# ESP-01_Tamer_-_V1_1.net
KiCad netlist of a schematic drawn in EAGLE
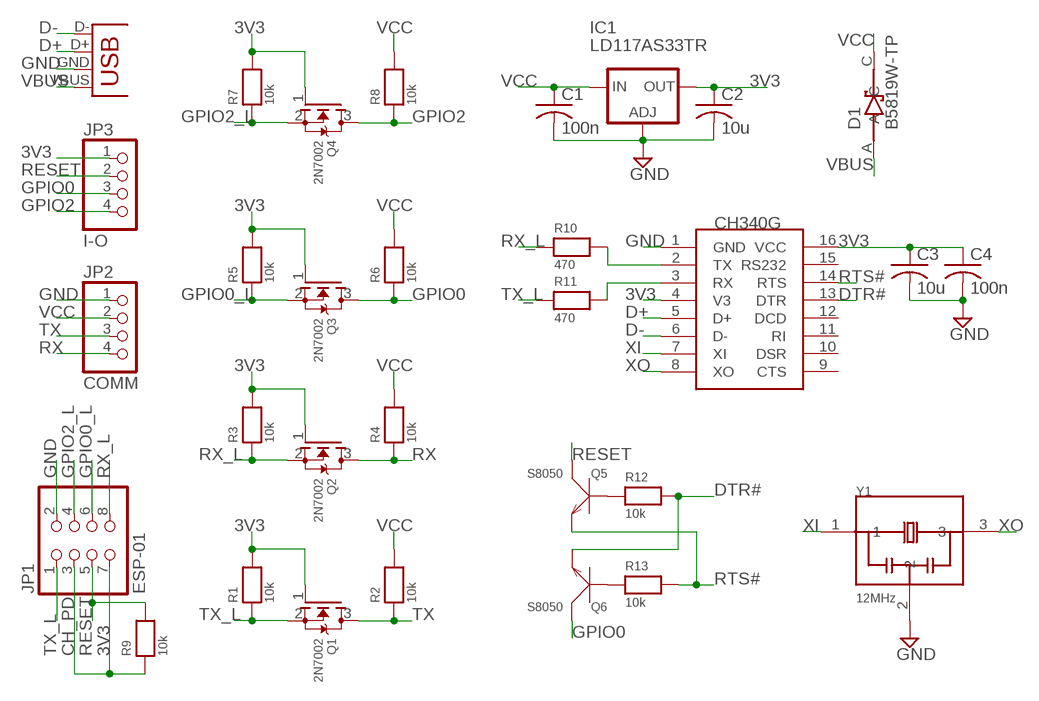
[diagram p0: schematic, sheet 1]

(export (version "E")
  (design (tool "Eeschema 10.0.6"))
  (components
    (comp (ref "C1")
      (value "100n")
      (footprint "eagle-import:C0805K")
      (libsource (lib "eagle-import") (part "C-USC0805K"))
    )
    (comp (ref "C2")
      (value "10u")
      (footprint "eagle-import:C0805K")
      (libsource (lib "eagle-import") (part "C-USC0805K"))
    )
    (comp (ref "C3")
      (value "10u")
      (footprint "eagle-import:C0805K")
      (libsource (lib "eagle-import") (part "C-USC0805K"))
    )
    (comp (ref "C4")
      (value "100n")
      (footprint "eagle-import:C0805K")
      (libsource (lib "eagle-import") (part "C-USC0805K"))
    )
    (comp (ref "D1")
      (value "B5819W-TP")
      (footprint "eagle-import:SOD3716X135N")
      (fields (field (name "MF") "Micro Commercial"))
      (libsource (lib "eagle-import") (part "B5819W-TP"))
    )
    (comp (ref "IC1")
      (value "LD117AS33TR")
      (footprint "eagle-import:SOT223")
      (libsource (lib "eagle-import") (part "LD117A?S33TR"))
    )
    (comp (ref "IC2")
      (value "CH340G")
      (footprint "eagle-import:SOIC16")
      (libsource (lib "eagle-import") (part "CH340G"))
    )
    (comp (ref "JP1")
      (value "ESP-01")
      (footprint "eagle-import:2X04")
      (libsource (lib "eagle-import") (part "PINHD-2X4"))
    )
    (comp (ref "JP2")
      (value "COMM")
      (footprint "eagle-import:1X04_ROUND")
      (libsource (lib "eagle-import") (part "HEADER-1X4ROUND"))
    )
    (comp (ref "JP3")
      (value "I-O")
      (footprint "eagle-import:1X04_ROUND")
      (libsource (lib "eagle-import") (part "HEADER-1X4ROUND"))
    )
    (comp (ref "JP4")
      (value "USB-A-H")
      (footprint "eagle-import:USB-A-H")
      (libsource (lib "eagle-import") (part "USB-A-H"))
    )
    (comp (ref "Q1")
      (value "2N7002")
      (footprint "eagle-import:SOT23-WIDE")
      (libsource (lib "eagle-import") (part "MOSFET-NWIDE"))
    )
    (comp (ref "Q2")
      (value "2N7002")
      (footprint "eagle-import:SOT23-WIDE")
      (libsource (lib "eagle-import") (part "MOSFET-NWIDE"))
    )
    (comp (ref "Q3")
      (value "2N7002")
      (footprint "eagle-import:SOT23-WIDE")
      (libsource (lib "eagle-import") (part "MOSFET-NWIDE"))
    )
    (comp (ref "Q4")
      (value "2N7002")
      (footprint "eagle-import:SOT23-WIDE")
      (libsource (lib "eagle-import") (part "MOSFET-NWIDE"))
    )
    (comp (ref "Q5")
      (value "S8050")
      (footprint "eagle-import:SOT-23")
      (fields (field (name "MF") "JCET"))
      (libsource (lib "eagle-import") (part "SMD-TRANSISTORS-NPN-25V-500MW-S8050(SOT-23)"))
    )
    (comp (ref "Q6")
      (value "S8050")
      (footprint "eagle-import:SOT-23")
      (fields (field (name "MF") "JCET"))
      (libsource (lib "eagle-import") (part "SMD-TRANSISTORS-NPN-25V-500MW-S8050(SOT-23)"))
    )
    (comp (ref "R1")
      (value "10k")
      (footprint "eagle-import:0805_NOTHERMALS")
      (libsource (lib "eagle-import") (part "RESISTOR0805_NOTHERMALS"))
    )
    (comp (ref "R2")
      (value "10k")
      (footprint "eagle-import:0805_NOTHERMALS")
      (libsource (lib "eagle-import") (part "RESISTOR0805_NOTHERMALS"))
    )
    (comp (ref "R3")
      (value "10k")
      (footprint "eagle-import:0805_NOTHERMALS")
      (libsource (lib "eagle-import") (part "RESISTOR0805_NOTHERMALS"))
    )
    (comp (ref "R4")
      (value "10k")
      (footprint "eagle-import:0805_NOTHERMALS")
      (libsource (lib "eagle-import") (part "RESISTOR0805_NOTHERMALS"))
    )
    (comp (ref "R5")
      (value "10k")
      (footprint "eagle-import:0805_NOTHERMALS")
      (libsource (lib "eagle-import") (part "RESISTOR0805_NOTHERMALS"))
    )
    (comp (ref "R6")
      (value "10k")
      (footprint "eagle-import:0805_NOTHERMALS")
      (libsource (lib "eagle-import") (part "RESISTOR0805_NOTHERMALS"))
    )
    (comp (ref "R7")
      (value "10k")
      (footprint "eagle-import:0805_NOTHERMALS")
      (libsource (lib "eagle-import") (part "RESISTOR0805_NOTHERMALS"))
    )
    (comp (ref "R8")
      (value "10k")
      (footprint "eagle-import:0805_NOTHERMALS")
      (libsource (lib "eagle-import") (part "RESISTOR0805_NOTHERMALS"))
    )
    (comp (ref "R9")
      (value "10k")
      (footprint "eagle-import:0805_NOTHERMALS")
      (libsource (lib "eagle-import") (part "RESISTOR0805_NOTHERMALS"))
    )
    (comp (ref "R10")
      (value "470")
      (footprint "eagle-import:0805_NOTHERMALS")
      (libsource (lib "eagle-import") (part "RESISTOR0805_NOTHERMALS"))
    )
    (comp (ref "R11")
      (value "470")
      (footprint "eagle-import:0805_NOTHERMALS")
      (libsource (lib "eagle-import") (part "RESISTOR0805_NOTHERMALS"))
    )
    (comp (ref "R12")
      (value "10k")
      (footprint "eagle-import:0805_NOTHERMALS")
      (libsource (lib "eagle-import") (part "RESISTOR0805_NOTHERMALS"))
    )
    (comp (ref "R13")
      (value "10k")
      (footprint "eagle-import:0805_NOTHERMALS")
      (libsource (lib "eagle-import") (part "RESISTOR0805_NOTHERMALS"))
    )
    (comp (ref "Y1")
      (value "12MHz")
      (footprint "eagle-import:OSC_CSTCE8M00G55-R0")
      (fields (field (name "MF") "Murata") (field (name "MP") "CSTCE8M00G55-R0"))
      (libsource (lib "eagle-import") (part "CSTCE8M00G55-R0"))
    )
  )
  (nets
    (net (code "1") (name "/3V3") (class "Default")
      (node (ref "C2") (pin "1") (pinfunction "1_1") (pintype "passive"))
      (node (ref "C3") (pin "1") (pinfunction "1_1") (pintype "passive"))
      (node (ref "C4") (pin "1") (pinfunction "1_1") (pintype "passive"))
      (node (ref "IC1") (pin "4") (pinfunction "OUT_4") (pintype "passive"))
      (node (ref "IC2") (pin "16") (pinfunction "VCC_16") (pintype "bidirectional"))
      (node (ref "IC2") (pin "4") (pinfunction "V3_4") (pintype "bidirectional"))
      (node (ref "JP1") (pin "3") (pinfunction "3_3") (pintype "passive"))
      (node (ref "JP1") (pin "7") (pinfunction "7_7") (pintype "passive"))
      (node (ref "JP3") (pin "1") (pinfunction "1_1") (pintype "passive"))
      (node (ref "Q1") (pin "1") (pinfunction "G_1") (pintype "bidirectional"))
      (node (ref "Q2") (pin "1") (pinfunction "G_1") (pintype "bidirectional"))
      (node (ref "Q3") (pin "1") (pinfunction "G_1") (pintype "bidirectional"))
      (node (ref "Q4") (pin "1") (pinfunction "G_1") (pintype "bidirectional"))
      (node (ref "R1") (pin "2") (pinfunction "2_2") (pintype "passive"))
      (node (ref "R3") (pin "2") (pinfunction "2_2") (pintype "passive"))
      (node (ref "R5") (pin "2") (pinfunction "2_2") (pintype "passive"))
      (node (ref "R7") (pin "2") (pinfunction "2_2") (pintype "passive"))
      (node (ref "R9") (pin "1") (pinfunction "1_1") (pintype "passive"))
    )
    (net (code "2") (name "/D+") (class "Default")
      (node (ref "IC2") (pin "5") (pinfunction "D+_5") (pintype "bidirectional"))
      (node (ref "JP4") (pin "D+") (pinfunction "D-_D+") (pintype "bidirectional"))
    )
    (net (code "3") (name "/D-") (class "Default")
      (node (ref "IC2") (pin "6") (pinfunction "D-_6") (pintype "bidirectional"))
      (node (ref "JP4") (pin "D-") (pinfunction "D+_D-") (pintype "bidirectional"))
    )
    (net (code "4") (name "/DTR#") (class "Default")
      (node (ref "IC2") (pin "13") (pinfunction "DTR_13") (pintype "bidirectional"))
      (node (ref "Q6") (pin "2") (pinfunction "E_2") (pintype "passive"))
      (node (ref "R12") (pin "2") (pinfunction "2_2") (pintype "passive"))
    )
    (net (code "5") (name "/GPIO0") (class "Default")
      (node (ref "JP3") (pin "3") (pinfunction "3_3") (pintype "passive"))
      (node (ref "Q3") (pin "3") (pinfunction "D_3") (pintype "bidirectional"))
      (node (ref "Q6") (pin "3") (pinfunction "C_3") (pintype "passive"))
      (node (ref "R6") (pin "1") (pinfunction "1_1") (pintype "passive"))
    )
    (net (code "6") (name "/GPIO0_L") (class "Default")
      (node (ref "JP1") (pin "6") (pinfunction "6_6") (pintype "passive"))
      (node (ref "Q3") (pin "2") (pinfunction "S_2") (pintype "bidirectional"))
      (node (ref "R5") (pin "1") (pinfunction "1_1") (pintype "passive"))
    )
    (net (code "7") (name "/GPIO2") (class "Default")
      (node (ref "JP3") (pin "4") (pinfunction "4_4") (pintype "passive"))
      (node (ref "Q4") (pin "3") (pinfunction "D_3") (pintype "bidirectional"))
      (node (ref "R8") (pin "1") (pinfunction "1_1") (pintype "passive"))
    )
    (net (code "8") (name "/GPIO2_L") (class "Default")
      (node (ref "JP1") (pin "4") (pinfunction "4_4") (pintype "passive"))
      (node (ref "Q4") (pin "2") (pinfunction "S_2") (pintype "bidirectional"))
      (node (ref "R7") (pin "1") (pinfunction "1_1") (pintype "passive"))
    )
    (net (code "9") (name "/RESET") (class "Default")
      (node (ref "JP1") (pin "5") (pinfunction "5_5") (pintype "passive"))
      (node (ref "JP3") (pin "2") (pinfunction "2_2") (pintype "passive"))
      (node (ref "Q5") (pin "3") (pinfunction "C_3") (pintype "passive"))
      (node (ref "R9") (pin "2") (pinfunction "2_2") (pintype "passive"))
    )
    (net (code "10") (name "/RTS#") (class "Default")
      (node (ref "IC2") (pin "14") (pinfunction "RTS_14") (pintype "bidirectional"))
      (node (ref "Q5") (pin "2") (pinfunction "E_2") (pintype "passive"))
      (node (ref "R13") (pin "2") (pinfunction "2_2") (pintype "passive"))
    )
    (net (code "11") (name "/RX") (class "Default")
      (node (ref "JP2") (pin "4") (pinfunction "4_4") (pintype "passive"))
      (node (ref "Q2") (pin "3") (pinfunction "D_3") (pintype "bidirectional"))
      (node (ref "R4") (pin "1") (pinfunction "1_1") (pintype "passive"))
    )
    (net (code "12") (name "/RX_L") (class "Default")
      (node (ref "JP1") (pin "8") (pinfunction "8_8") (pintype "passive"))
      (node (ref "Q2") (pin "2") (pinfunction "S_2") (pintype "bidirectional"))
      (node (ref "R10") (pin "1") (pinfunction "1_1") (pintype "passive"))
      (node (ref "R3") (pin "1") (pinfunction "1_1") (pintype "passive"))
    )
    (net (code "13") (name "/TX") (class "Default")
      (node (ref "JP2") (pin "3") (pinfunction "3_3") (pintype "passive"))
      (node (ref "Q1") (pin "3") (pinfunction "D_3") (pintype "bidirectional"))
      (node (ref "R2") (pin "1") (pinfunction "1_1") (pintype "passive"))
    )
    (net (code "14") (name "/TX_L") (class "Default")
      (node (ref "JP1") (pin "1") (pinfunction "1_1") (pintype "passive"))
      (node (ref "Q1") (pin "2") (pinfunction "S_2") (pintype "bidirectional"))
      (node (ref "R1") (pin "1") (pinfunction "1_1") (pintype "passive"))
      (node (ref "R11") (pin "1") (pinfunction "1_1") (pintype "passive"))
    )
    (net (code "15") (name "/VBUS") (class "Default")
      (node (ref "D1") (pin "A") (pinfunction "A_A") (pintype "passive"))
      (node (ref "JP4") (pin "VBUS") (pinfunction "GND_VBUS") (pintype "bidirectional"))
    )
    (net (code "16") (name "/VCC") (class "Default")
      (node (ref "C1") (pin "1") (pinfunction "1_1") (pintype "passive"))
      (node (ref "D1") (pin "C") (pinfunction "C_C") (pintype "passive"))
      (node (ref "IC1") (pin "3") (pinfunction "IN_3") (pintype "input"))
      (node (ref "JP2") (pin "2") (pinfunction "2_2") (pintype "passive"))
      (node (ref "R2") (pin "2") (pinfunction "2_2") (pintype "passive"))
      (node (ref "R4") (pin "2") (pinfunction "2_2") (pintype "passive"))
      (node (ref "R6") (pin "2") (pinfunction "2_2") (pintype "passive"))
      (node (ref "R8") (pin "2") (pinfunction "2_2") (pintype "passive"))
    )
    (net (code "17") (name "/XI") (class "Default")
      (node (ref "IC2") (pin "7") (pinfunction "XI_7") (pintype "bidirectional"))
      (node (ref "Y1") (pin "1") (pinfunction "1_1") (pintype "passive"))
    )
    (net (code "18") (name "/XO") (class "Default")
      (node (ref "IC2") (pin "8") (pinfunction "XO_8") (pintype "bidirectional"))
      (node (ref "Y1") (pin "3") (pinfunction "3_3") (pintype "passive"))
    )
    (net (code "19") (name "GND") (class "Default")
      (node (ref "C1") (pin "2") (pinfunction "2_2") (pintype "passive"))
      (node (ref "C2") (pin "2") (pinfunction "2_2") (pintype "passive"))
      (node (ref "C3") (pin "2") (pinfunction "2_2") (pintype "passive"))
      (node (ref "C4") (pin "2") (pinfunction "2_2") (pintype "passive"))
      (node (ref "IC1") (pin "1") (pinfunction "ADJ_1") (pintype "input"))
      (node (ref "IC2") (pin "1") (pinfunction "GND_1") (pintype "bidirectional"))
      (node (ref "JP1") (pin "2") (pinfunction "2_2") (pintype "passive"))
      (node (ref "JP2") (pin "1") (pinfunction "1_1") (pintype "passive"))
      (node (ref "JP4") (pin "GND") (pinfunction "VBUS_GND") (pintype "bidirectional"))
      (node (ref "Y1") (pin "2") (pinfunction "2_2") (pintype "power_in"))
    )
    (net (code "20") (name "Net-(IC2-RX)") (class "Default")
      (node (ref "IC2") (pin "3") (pinfunction "RX_3") (pintype "bidirectional"))
      (node (ref "R11") (pin "2") (pinfunction "2_2") (pintype "passive"))
    )
    (net (code "21") (name "Net-(IC2-TX)") (class "Default")
      (node (ref "IC2") (pin "2") (pinfunction "TX_2") (pintype "bidirectional"))
      (node (ref "R10") (pin "2") (pinfunction "2_2") (pintype "passive"))
    )
    (net (code "22") (name "Net-(Q5-B)") (class "Default")
      (node (ref "Q5") (pin "1") (pinfunction "B_1") (pintype "passive"))
      (node (ref "R12") (pin "1") (pinfunction "1_1") (pintype "passive"))
    )
    (net (code "23") (name "Net-(Q6-B)") (class "Default")
      (node (ref "Q6") (pin "1") (pinfunction "B_1") (pintype "passive"))
      (node (ref "R13") (pin "1") (pinfunction "1_1") (pintype "passive"))
    )
    (net (code "24") (name "unconnected-(IC2-CTS-Pad9)") (class "Default")
      (node (ref "IC2") (pin "9") (pinfunction "CTS_9") (pintype "bidirectional"))
    )
    (net (code "25") (name "unconnected-(IC2-DCD-Pad12)") (class "Default")
      (node (ref "IC2") (pin "12") (pinfunction "DCD_12") (pintype "bidirectional"))
    )
    (net (code "26") (name "unconnected-(IC2-DSR-Pad10)") (class "Default")
      (node (ref "IC2") (pin "10") (pinfunction "DSR_10") (pintype "bidirectional"))
    )
    (net (code "27") (name "unconnected-(IC2-RI-Pad11)") (class "Default")
      (node (ref "IC2") (pin "11") (pinfunction "RI_11") (pintype "bidirectional"))
    )
    (net (code "28") (name "unconnected-(IC2-RS232-Pad15)") (class "Default")
      (node (ref "IC2") (pin "15") (pinfunction "RS232_15") (pintype "bidirectional"))
    )
  )
)
